# logi-cam.net
KiCad netlist of a schematic drawn in Altium Designer
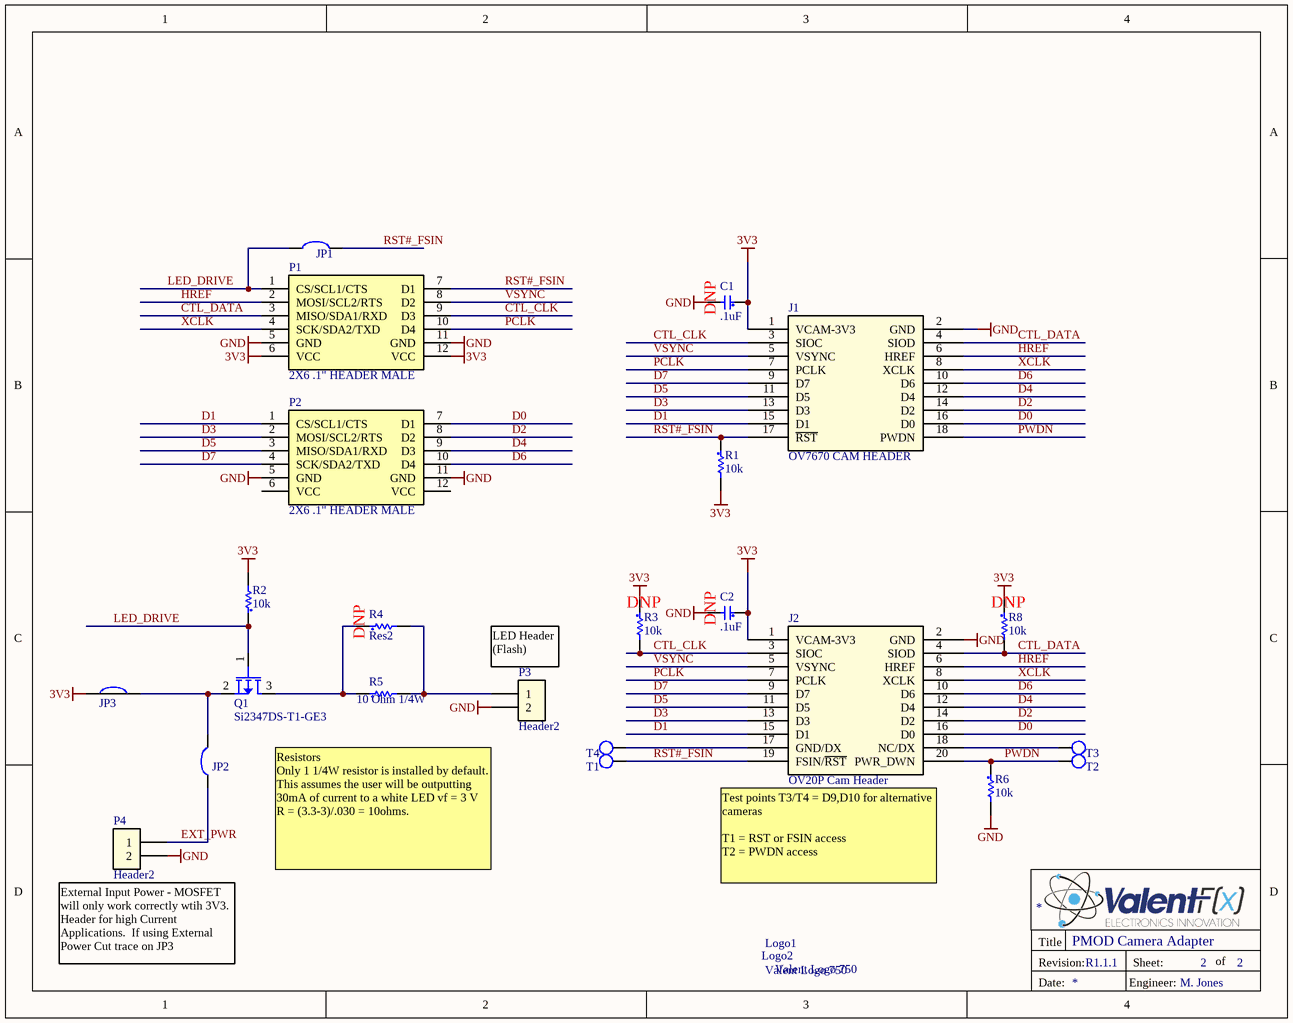
[diagram p0: logi-cam.SchDoc]

(export (version "E")
  (design (tool "Eeschema 10.0.6"))
  (components
    (comp (ref "C1")
      (value ".1uF")
      (footprint "mRCL:C0603")
      (description ".10uF X7R 20% (MLCC) - SMD/SMT 0603 25volts")
      (fields (field (name "MANUFACTURER") "TDK") (field (name "MANUFACTURER PART NUMBER") "C1608X7R1E104MT"))
      (libsource (lib "mCapacitors") (part "C0603 - C1608X7R1E104MT"))
    )
    (comp (ref "C2")
      (value ".1uF")
      (footprint "mRCL:C0603")
      (description ".10uF X7R 20% (MLCC) - SMD/SMT 0603 25volts")
      (fields (field (name "MANUFACTURER") "TDK") (field (name "MANUFACTURER PART NUMBER") "C1608X7R1E104MT"))
      (libsource (lib "mCapacitors") (part "C0603 - C1608X7R1E104MT"))
    )
    (comp (ref "J1")
      (value "OV7670 CAM HEADER")
      (footprint "HEADER_9x2_40_100 1-3-5 THRU DIP")
      (description "CONN HEADER FMAL 18PS .1\" DL GOLD")
      (fields
        (field (name "MANUFACTURER") "Sullins Connector Solutions")
        (field (name "MANUFACTURER PART NUMBER") "PPPC092LFBN-RC")
      )
      (libsource (lib "mModule") (part "CAM - OV7670"))
    )
    (comp (ref "J2")
      (value "OV20P Cam Header")
      (footprint "HEADER_10x2_40_100 1-3-5 THRU DIP")
      (description "CONN HEADR FMALE 20 POS .1\" DL AU")
      (fields
        (field (name "MANUFACTURER") "Sullins Connector Solutions")
        (field (name "MANUFACTURER PART NUMBER") "PPPC102LFBN-RC")
      )
      (libsource (lib "mModule") (part "CAM - 0V20P"))
    )
    (comp (ref "JP1")
      (value "Solder Jumper")
      (footprint "SOLDER_JUMPER")
      (description "Solder/Configuration Jumper")
      (fields (field (name "MANUFACTURER") "n/a"))
      (libsource (lib "") (part "Solder Jumper_1"))
    )
    (comp (ref "JP2")
      (value "Solder Jumper")
      (footprint "SOLDER_JUMPER")
      (description "Solder/Configuration Jumper")
      (fields (field (name "MANUFACTURER") "n/a"))
      (libsource (lib "mConnector") (part "Solder Jumper"))
    )
    (comp (ref "JP3")
      (value "Solder Jumper-NC")
      (footprint "SOLDER_JUMPER-NC")
      (description "Solder/Configuration Jumper")
      (fields (field (name "MANUFACTURER") "n/a"))
      (libsource (lib "mConnector") (part "Solder Jumper-NC"))
    )
    (comp (ref "Logo1")
      (value "Valent Logo 750")
      (footprint "VALENTFX_750-SolderMask-BOT")
      (libsource (lib "mLogos") (part "Valent Logo 750"))
    )
    (comp (ref "Logo2")
      (value "Valent Logo 750")
      (footprint "VALENTFX_750-SolderMask-BOT")
      (libsource (lib "mLogos") (part "Valent Logo 750"))
    )
    (comp (ref "P1")
      (value "2X6 .1\" HEADER MALE")
      (footprint "PMOD HEADER - Male Vertical")
      (description "CONN HEADER .100\" DUAL STR 12 POS")
      (fields
        (field (name "MANUFACTURER") "Sullins Connector Solutions")
        (field (name "MANUFACTURER PART NUMBER") "PRPC006DAAN-RC")
      )
      (libsource (lib "mConnector") (part "P-MOD - PRPC006DAAN-RC"))
    )
    (comp (ref "P2")
      (value "2X6 .1\" HEADER MALE")
      (footprint "PMOD HEADER - Male Vertical")
      (description "CONN HEADER .100\" DUAL STR 12 POS")
      (fields
        (field (name "MANUFACTURER") "Sullins Connector Solutions")
        (field (name "MANUFACTURER PART NUMBER") "PRPC006DAAN-RC")
      )
      (libsource (lib "mConnector") (part "P-MOD - PRPC006DAAN-RC"))
    )
    (comp (ref "P3")
      (value "Header2")
      (footprint "HEADER_2_40_100 THRU SIP")
      (description "Header 2 pin")
      (libsource (lib "mConnector") (part "Header2"))
    )
    (comp (ref "P4")
      (value "Header2")
      (footprint "HEADER_2_40_100 THRU SIP")
      (description "Header 2 pin")
      (libsource (lib "") (part "Header2_1"))
    )
    (comp (ref "Q1")
      (value "Si2347DS-T1-GE3")
      (footprint "sot-23")
      (description "MOSFET -30V .042Ohm@10V 5A P-Ch G-III")
      (fields
        (field (name "MANUFACTURER") "Vishay Semiconductors")
        (field (name "ACCEPT COMPATIBLE REPLACEMENT PART") "Yes")
      )
      (libsource (lib "mTransistor") (part "PMOS - Si2347DS-T1-GE3"))
    )
    (comp (ref "R1")
      (value "10k")
      (footprint "mRCL:R0603")
      (description "10k Thick Film Resistors - SMD 1/10watt 10Kohms 1%")
      (fields
        (field (name "MANUFACTURER") "Vishay Dale")
        (field (name "MANUFACTURER PART NUMBER") "CRCW060310K0FKEA")
      )
      (libsource (lib "mResistors") (part "R0603 - CRCW060310K0FKEA"))
    )
    (comp (ref "R2")
      (value "10k")
      (footprint "mRCL:R0603")
      (description "10k Thick Film Resistors - SMD 1/10watt 10Kohms 1%")
      (fields
        (field (name "MANUFACTURER") "Vishay Dale")
        (field (name "MANUFACTURER PART NUMBER") "CRCW060310K0FKEA")
      )
      (libsource (lib "mResistors") (part "R0603 - CRCW060310K0FKEA"))
    )
    (comp (ref "R3")
      (value "10k")
      (footprint "mRCL:R0603")
      (description "10k Thick Film Resistors - SMD 1/10watt 10Kohms 1%")
      (fields
        (field (name "MANUFACTURER") "Vishay Dale")
        (field (name "MANUFACTURER PART NUMBER") "CRCW060310K0FKEA")
      )
      (libsource (lib "mResistors") (part "R0603 - CRCW060310K0FKEA"))
    )
    (comp (ref "R4")
      (value "Res2")
      (footprint "mrcl:AXIAL-0.4")
      (description "1/4W .4 Axial")
      (libsource (lib "mResistors") (part "Res2"))
    )
    (comp (ref "R5")
      (value "10 Ohm 1/4W")
      (footprint "AXIAL-0.4")
      (description "Metal Film Resistors - Through Hole 10ohms 1% 100PPM")
      (fields
        (field (name "MANUFACTURER") "KOA Speer")
        (field (name "MANUFACTURER PART NUMBER") "MF1/4DCT52R10R0F2")
      )
      (libsource (lib "mResistors") (part "AX_25 - MF1/4DCT52R10R0F2"))
    )
    (comp (ref "R6")
      (value "10k")
      (footprint "mRCL:R0603")
      (description "10k Thick Film Resistors - SMD 1/10watt 10Kohms 1%")
      (fields
        (field (name "MANUFACTURER") "Vishay Dale")
        (field (name "MANUFACTURER PART NUMBER") "CRCW060310K0FKEA")
      )
      (libsource (lib "mResistors") (part "R0603 - CRCW060310K0FKEA"))
    )
    (comp (ref "R8")
      (value "10k")
      (footprint "mRCL:R0603")
      (description "10k Thick Film Resistors - SMD 1/10watt 10Kohms 1%")
      (fields
        (field (name "MANUFACTURER") "Vishay Dale")
        (field (name "MANUFACTURER PART NUMBER") "CRCW060310K0FKEA")
      )
      (libsource (lib "mResistors") (part "R0603 - CRCW060310K0FKEA"))
    )
    (comp (ref "T1")
      (value "Test Point")
      (footprint "Tp 35-50")
      (description "Test Point Smaller Symbol")
      (libsource (lib "mConnector") (part "Test Point 2"))
    )
    (comp (ref "T2")
      (value "Test Point")
      (footprint "Tp 35-50")
      (description "Test Point Smaller Symbol")
      (libsource (lib "mConnector") (part "Test Point 2"))
    )
    (comp (ref "T3")
      (value "Test Point")
      (footprint "Tp 35-50")
      (description "Test Point Smaller Symbol")
      (libsource (lib "mConnector") (part "Test Point 2"))
    )
    (comp (ref "T4")
      (value "Test Point")
      (footprint "Tp 35-50")
      (description "Test Point Smaller Symbol")
      (libsource (lib "") (part "Test Point 2_1"))
    )
  )
  (nets
    (net (code "1") (name "/CTL_CLK") (class "Default")
      (node (ref "J1") (pin "3") (pinfunction "SIOC_3") (pintype "passive"))
      (node (ref "J2") (pin "3") (pinfunction "SIOC_3") (pintype "passive"))
      (node (ref "P1") (pin "9") (pinfunction "D3_9") (pintype "power_in"))
      (node (ref "R3") (pin "2") (pinfunction "2_2") (pintype "passive"))
    )
    (net (code "2") (name "/CTL_DATA") (class "Default")
      (node (ref "J1") (pin "4") (pinfunction "SIOD_4") (pintype "passive"))
      (node (ref "J2") (pin "4") (pinfunction "SIOD_4") (pintype "passive"))
      (node (ref "P1") (pin "3") (pinfunction "MISO/SDA1/RXD_3") (pintype "power_in"))
      (node (ref "R8") (pin "2") (pinfunction "2_2") (pintype "passive"))
    )
    (net (code "3") (name "/D0") (class "Default")
      (node (ref "J1") (pin "16") (pinfunction "D0_16") (pintype "passive"))
      (node (ref "J2") (pin "16") (pinfunction "D0_16") (pintype "passive"))
      (node (ref "P2") (pin "7") (pinfunction "D1_7") (pintype "power_in"))
    )
    (net (code "4") (name "/D1") (class "Default")
      (node (ref "J1") (pin "15") (pinfunction "D1_15") (pintype "passive"))
      (node (ref "J2") (pin "15") (pinfunction "D1_15") (pintype "passive"))
      (node (ref "P2") (pin "1") (pinfunction "CS/SCL1/CTS_1") (pintype "power_in"))
    )
    (net (code "5") (name "/D2") (class "Default")
      (node (ref "J1") (pin "14") (pinfunction "D2_14") (pintype "passive"))
      (node (ref "J2") (pin "14") (pinfunction "D2_14") (pintype "passive"))
      (node (ref "P2") (pin "8") (pinfunction "D2_8") (pintype "power_in"))
    )
    (net (code "6") (name "/D3") (class "Default")
      (node (ref "J1") (pin "13") (pinfunction "D3_13") (pintype "passive"))
      (node (ref "J2") (pin "13") (pinfunction "D3_13") (pintype "passive"))
      (node (ref "P2") (pin "2") (pinfunction "MOSI/SCL2/RTS_2") (pintype "power_in"))
    )
    (net (code "7") (name "/D4") (class "Default")
      (node (ref "J1") (pin "12") (pinfunction "D4_12") (pintype "passive"))
      (node (ref "J2") (pin "12") (pinfunction "D4_12") (pintype "passive"))
      (node (ref "P2") (pin "9") (pinfunction "D3_9") (pintype "power_in"))
    )
    (net (code "8") (name "/D5") (class "Default")
      (node (ref "J1") (pin "11") (pinfunction "D5_11") (pintype "passive"))
      (node (ref "J2") (pin "11") (pinfunction "D5_11") (pintype "passive"))
      (node (ref "P2") (pin "3") (pinfunction "MISO/SDA1/RXD_3") (pintype "power_in"))
    )
    (net (code "9") (name "/D6") (class "Default")
      (node (ref "J1") (pin "10") (pinfunction "D6_10") (pintype "passive"))
      (node (ref "J2") (pin "10") (pinfunction "D6_10") (pintype "passive"))
      (node (ref "P2") (pin "10") (pinfunction "D4_10") (pintype "power_in"))
    )
    (net (code "10") (name "/D7") (class "Default")
      (node (ref "J1") (pin "9") (pinfunction "D7_9") (pintype "passive"))
      (node (ref "J2") (pin "9") (pinfunction "D7_9") (pintype "passive"))
      (node (ref "P2") (pin "4") (pinfunction "SCK/SDA2/TXD_4") (pintype "power_in"))
    )
    (net (code "11") (name "/EXT_PWR") (class "Default")
      (node (ref "JP2") (pin "1") (pinfunction "1_1") (pintype "passive"))
      (node (ref "P4") (pin "1") (pinfunction "1_1") (pintype "passive"))
    )
    (net (code "12") (name "/HREF") (class "Default")
      (node (ref "J1") (pin "6") (pinfunction "HREF_6") (pintype "passive"))
      (node (ref "J2") (pin "6") (pinfunction "HREF_6") (pintype "passive"))
      (node (ref "P1") (pin "2") (pinfunction "MOSI/SCL2/RTS_2") (pintype "power_in"))
    )
    (net (code "13") (name "/LED_DRIVE") (class "Default")
      (node (ref "JP1") (pin "1") (pinfunction "1_1") (pintype "passive"))
      (node (ref "P1") (pin "1") (pinfunction "CS/SCL1/CTS_1") (pintype "power_in"))
      (node (ref "Q1") (pin "1") (pinfunction "G_1") (pintype "passive"))
      (node (ref "R2") (pin "1") (pinfunction "1_1") (pintype "passive"))
    )
    (net (code "14") (name "/PCLK") (class "Default")
      (node (ref "J1") (pin "7") (pinfunction "PCLK_7") (pintype "passive"))
      (node (ref "J2") (pin "7") (pinfunction "PCLK_7") (pintype "passive"))
      (node (ref "P1") (pin "10") (pinfunction "D4_10") (pintype "power_in"))
    )
    (net (code "15") (name "/PWDN") (class "Default")
      (node (ref "J1") (pin "18") (pinfunction "PWDN_18") (pintype "passive"))
      (node (ref "J2") (pin "20") (pinfunction "PWR_DWN_20") (pintype "passive"))
      (node (ref "R6") (pin "1") (pinfunction "1_1") (pintype "passive"))
      (node (ref "T2") (pin "1") (pinfunction "1_1") (pintype "passive"))
    )
    (net (code "16") (name "/RST#_FSIN") (class "Default")
      (node (ref "J1") (pin "17") (pinfunction "~{RST}_17") (pintype "passive"))
      (node (ref "J2") (pin "19") (pinfunction "FSIN/~{RST}_19") (pintype "passive"))
      (node (ref "JP1") (pin "2") (pinfunction "2_2") (pintype "passive"))
      (node (ref "P1") (pin "7") (pinfunction "D1_7") (pintype "power_in"))
      (node (ref "R1") (pin "1") (pinfunction "1_1") (pintype "passive"))
      (node (ref "T1") (pin "1") (pinfunction "1_1") (pintype "passive"))
    )
    (net (code "17") (name "/VSYNC") (class "Default")
      (node (ref "J1") (pin "5") (pinfunction "VSYNC_5") (pintype "passive"))
      (node (ref "J2") (pin "5") (pinfunction "VSYNC_5") (pintype "passive"))
      (node (ref "P1") (pin "8") (pinfunction "D2_8") (pintype "power_in"))
    )
    (net (code "18") (name "/XCLK") (class "Default")
      (node (ref "J1") (pin "8") (pinfunction "XCLK_8") (pintype "passive"))
      (node (ref "J2") (pin "8") (pinfunction "XCLK_8") (pintype "passive"))
      (node (ref "P1") (pin "4") (pinfunction "SCK/SDA2/TXD_4") (pintype "power_in"))
    )
    (net (code "19") (name "3V3") (class "Default")
      (node (ref "C1") (pin "1") (pinfunction "1_1") (pintype "passive"))
      (node (ref "C2") (pin "1") (pinfunction "1_1") (pintype "passive"))
      (node (ref "J1") (pin "1") (pinfunction "VCAM-3V3_1") (pintype "passive"))
      (node (ref "J2") (pin "1") (pinfunction "VCAM-3V3_1") (pintype "passive"))
      (node (ref "JP3") (pin "1") (pinfunction "1_1") (pintype "passive"))
      (node (ref "P1") (pin "12") (pinfunction "VCC_12") (pintype "power_in"))
      (node (ref "P1") (pin "6") (pinfunction "VCC_6") (pintype "power_in"))
      (node (ref "R1") (pin "2") (pinfunction "2_2") (pintype "passive"))
      (node (ref "R2") (pin "2") (pinfunction "2_2") (pintype "passive"))
      (node (ref "R3") (pin "1") (pinfunction "1_1") (pintype "passive"))
      (node (ref "R8") (pin "1") (pinfunction "1_1") (pintype "passive"))
    )
    (net (code "20") (name "GND") (class "Default")
      (node (ref "C1") (pin "2") (pinfunction "2_2") (pintype "passive"))
      (node (ref "C2") (pin "2") (pinfunction "2_2") (pintype "passive"))
      (node (ref "J1") (pin "2") (pinfunction "GND_2") (pintype "passive"))
      (node (ref "J2") (pin "2") (pinfunction "GND_2") (pintype "passive"))
      (node (ref "P1") (pin "11") (pinfunction "GND_11") (pintype "power_in"))
      (node (ref "P1") (pin "5") (pinfunction "GND_5") (pintype "power_in"))
      (node (ref "P2") (pin "11") (pinfunction "GND_11") (pintype "power_in"))
      (node (ref "P2") (pin "5") (pinfunction "GND_5") (pintype "power_in"))
      (node (ref "P3") (pin "2") (pinfunction "2_2") (pintype "passive"))
      (node (ref "P4") (pin "2") (pinfunction "2_2") (pintype "passive"))
      (node (ref "R6") (pin "2") (pinfunction "2_2") (pintype "passive"))
    )
    (net (code "21") (name "Net-(J2-GND{slash}DX)") (class "Default")
      (node (ref "J2") (pin "17") (pinfunction "GND/DX_17") (pintype "passive"))
      (node (ref "T4") (pin "1") (pinfunction "1_1") (pintype "passive"))
    )
    (net (code "22") (name "Net-(J2-NC{slash}DX)") (class "Default")
      (node (ref "J2") (pin "18") (pinfunction "NC/DX_18") (pintype "passive"))
      (node (ref "T3") (pin "1") (pinfunction "1_1") (pintype "passive"))
    )
    (net (code "23") (name "Net-(P3-Pad1)") (class "Default")
      (node (ref "P3") (pin "1") (pinfunction "1_1") (pintype "passive"))
      (node (ref "R4") (pin "2") (pinfunction "2_2") (pintype "passive"))
      (node (ref "R5") (pin "2") (pinfunction "2_2") (pintype "passive"))
    )
    (net (code "24") (name "Net-(Q1-D)") (class "Default")
      (node (ref "Q1") (pin "3") (pinfunction "D_3") (pintype "passive"))
      (node (ref "R4") (pin "1") (pinfunction "1_1") (pintype "passive"))
      (node (ref "R5") (pin "1") (pinfunction "1_1") (pintype "passive"))
    )
    (net (code "25") (name "Net-(Q1-S)") (class "Default")
      (node (ref "JP2") (pin "2") (pinfunction "2_2") (pintype "passive"))
      (node (ref "JP3") (pin "2") (pinfunction "2_2") (pintype "passive"))
      (node (ref "Q1") (pin "2") (pinfunction "S_2") (pintype "passive"))
    )
    (net (code "26") (name "unconnected-(P2-VCC-Pad6)") (class "Default")
      (node (ref "P2") (pin "6") (pinfunction "VCC_6") (pintype "power_in"))
    )
    (net (code "27") (name "unconnected-(P2-VCC-Pad12)") (class "Default")
      (node (ref "P2") (pin "12") (pinfunction "VCC_12") (pintype "power_in"))
    )
  )
)
